# ModdedTSCircuit.net
KiCad netlist of a schematic drawn in Altium Designer
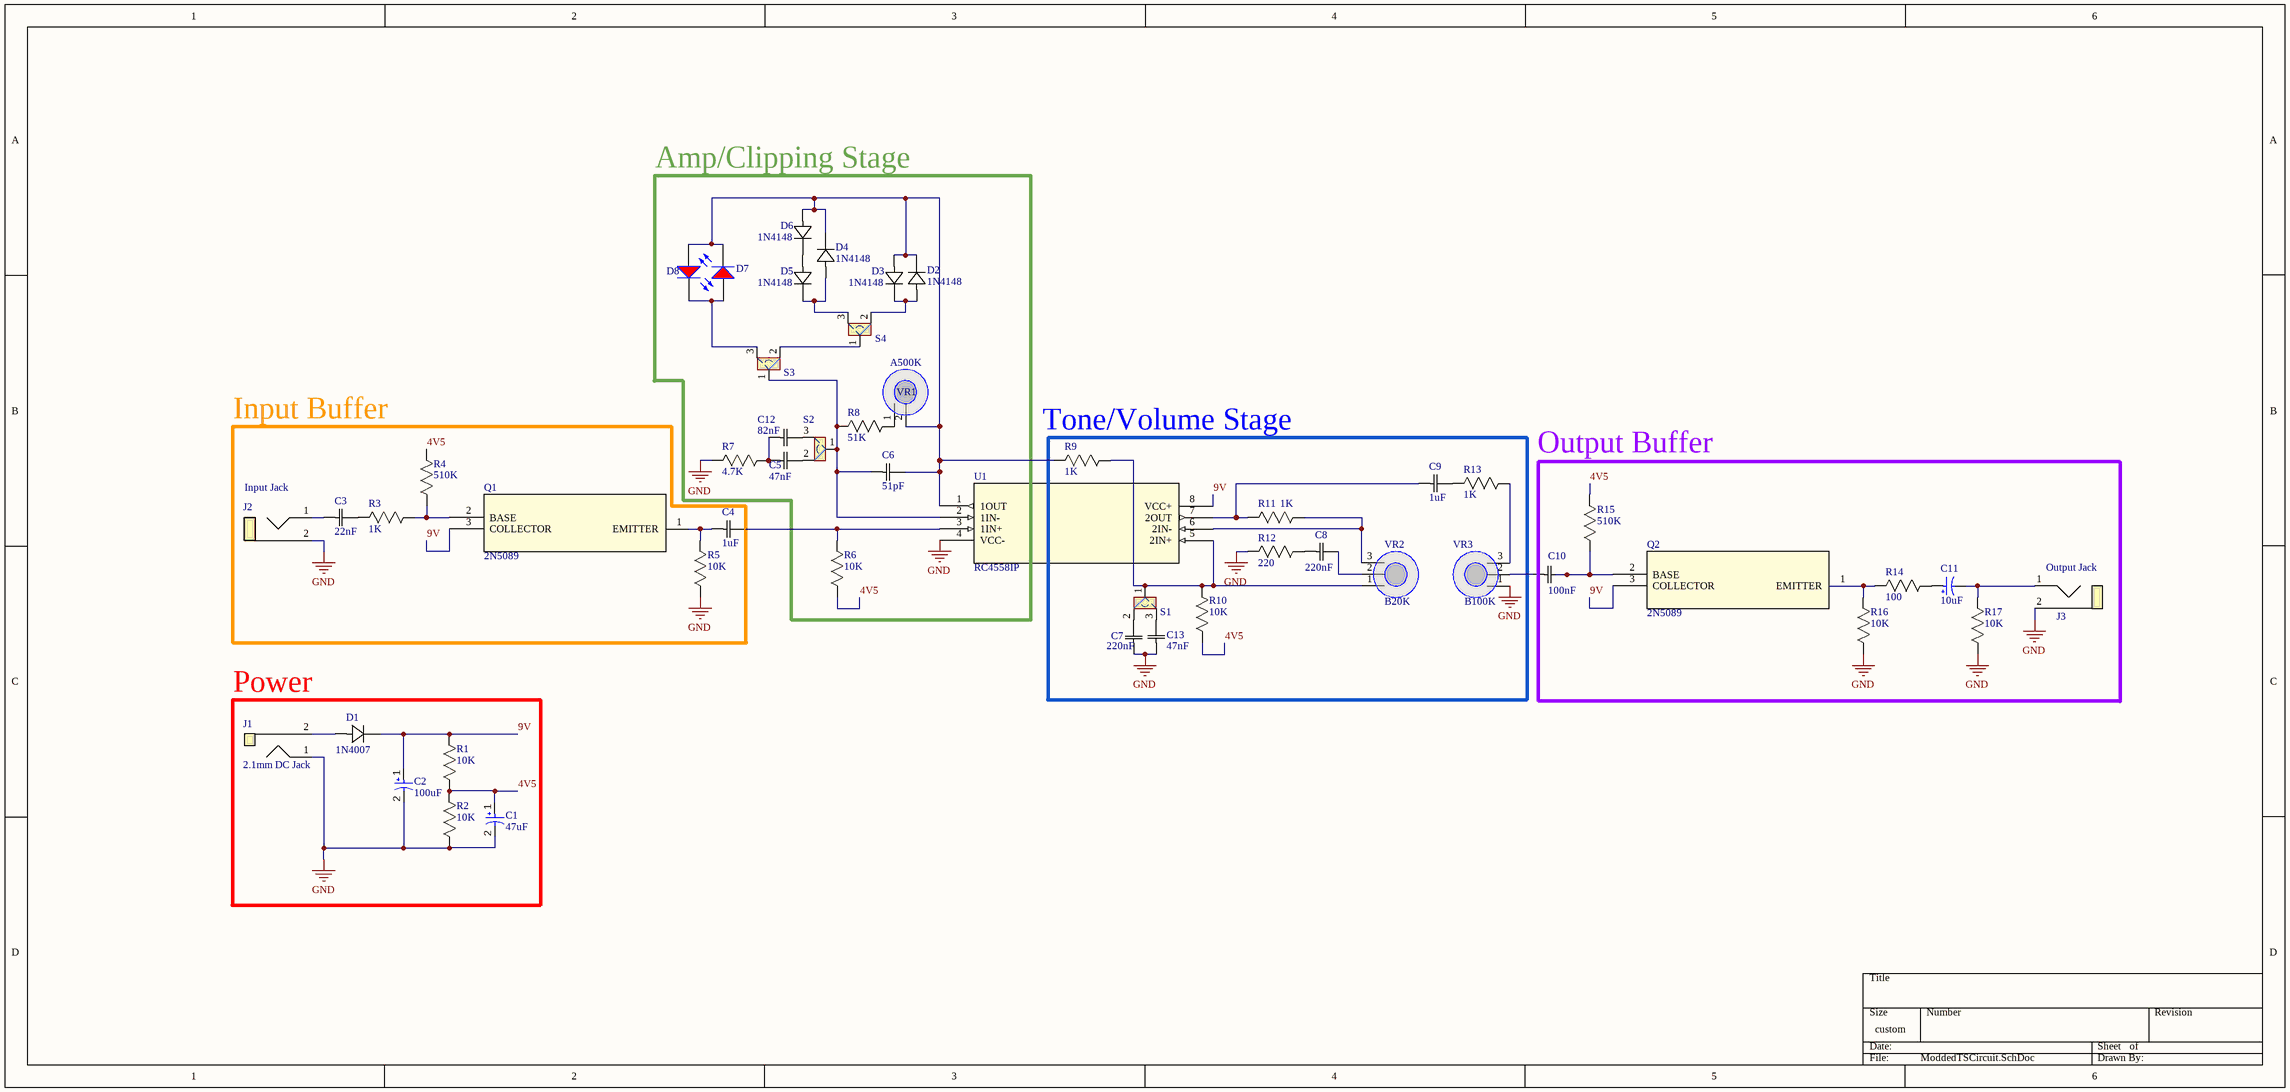
[diagram p0: ModdedTSCircuit.SchDoc]

(export (version "E")
  (design (tool "Eeschema 10.0.6"))
  (components
    (comp (ref "C1")
      (value "47uF")
      (footprint "CAP_35YXJ47M5X11")
      (description "47 µF 35 V Aluminum Electrolytic Capacitors Radial, Can 5000 Hrs @ 105°C")
      (fields
        (field (name "MANUFACTURER_PART_NUMBER") "35YXJ47M5X11")
        (field (name "COPYRIGHT") "Copyright (C) 2026 Ultra Librarian. All rights reserved.")
      )
      (libsource (lib "ModdedTSPartSymbols") (part "35YXJ47M5X11"))
    )
    (comp (ref "C2")
      (value "100uF")
      (footprint "CAP_25PX100MEFC5X11")
      (description "100 µF 25 V Aluminum Electrolytic Capacitors Radial, Can 1000 Hrs @ 105°C")
      (fields
        (field (name "MANUFACTURER_PART_NUMBER") "25PX100MEFC5X11")
        (field (name "COPYRIGHT") "Copyright (C) 2025 Ultra Librarian. All rights reserved.")
      )
      (libsource (lib "ModdedTSPartSymbols") (part "25PX100MEFC5X11"))
    )
    (comp (ref "C3")
      (value "22nF")
      (footprint "CAP_R82EC2220SH50J")
      (fields
        (field (name "MANUFACTURER_PART_NUMBER") "R82EC2220SH50J")
        (field (name "COPYRIGHT") "Copyright (C) 2026 Ultra Librarian. All rights reserved.")
      )
      (libsource (lib "ModdedTSPartSymbols") (part "R82EC2220SH50J"))
    )
    (comp (ref "C4")
      (value "1uF")
      (footprint "CAP_R82DC4100AA60K")
      (fields
        (field (name "MANUFACTURER_PART_NUMBER") "R82DC4100AA60K")
        (field (name "COPYRIGHT") "Copyright (C) 2026 Ultra Librarian. All rights reserved.")
      )
      (libsource (lib "ModdedTSPartSymbols") (part "R82DC4100AA60K"))
    )
    (comp (ref "C5")
      (value "47nF")
      (footprint "CAP_R82EC2470SH60J")
      (fields
        (field (name "MANUFACTURER_PART_NUMBER") "R82EC2470SH60J")
        (field (name "COPYRIGHT") "Copyright (C) 2026 Ultra Librarian. All rights reserved.")
      )
      (libsource (lib "ModdedTSPartSymbols") (part "R82EC2470SH60J"))
    )
    (comp (ref "C6")
      (value "51pF")
      (footprint "CAP_C315C510K3G5TA")
      (description "51 pF ±10% 25V Ceramic Capacitor C0G, NP0 Radial")
      (fields
        (field (name "MANUFACTURER_PART_NUMBER") "C315C510K3G5TA")
        (field (name "COPYRIGHT") "Copyright (C) 2026 Ultra Librarian. All rights reserved.")
      )
      (libsource (lib "ModdedTSPartSymbols") (part "C315C510K3G5TA"))
    )
    (comp (ref "C7")
      (value "220nF")
      (footprint "CAP_R82DC3220Z360J")
      (fields
        (field (name "MANUFACTURER_PART_NUMBER") "R82DC3220Z360J")
        (field (name "COPYRIGHT") "Copyright (C) 2026 Ultra Librarian. All rights reserved.")
      )
      (libsource (lib "ModdedTSPartSymbols") (part "R82DC3220Z360J"))
    )
    (comp (ref "C8")
      (value "220nF")
      (footprint "CAP_R82DC3220Z360J")
      (fields
        (field (name "MANUFACTURER_PART_NUMBER") "R82DC3220Z360J")
        (field (name "COPYRIGHT") "Copyright (C) 2026 Ultra Librarian. All rights reserved.")
      )
      (libsource (lib "ModdedTSPartSymbols") (part "R82DC3220Z360J"))
    )
    (comp (ref "C9")
      (value "1uF")
      (footprint "CAP_R82DC4100AA60K")
      (fields
        (field (name "MANUFACTURER_PART_NUMBER") "R82DC4100AA60K")
        (field (name "COPYRIGHT") "Copyright (C) 2026 Ultra Librarian. All rights reserved.")
      )
      (libsource (lib "ModdedTSPartSymbols") (part "R82DC4100AA60K"))
    )
    (comp (ref "C10")
      (value "100nF")
      (footprint "CAP_R82DC3100AA50K")
      (fields
        (field (name "MANUFACTURER_PART_NUMBER") "R82DC3100AA50K")
        (field (name "COPYRIGHT") "Copyright (C) 2026 Ultra Librarian. All rights reserved.")
      )
      (libsource (lib "ModdedTSPartSymbols") (part "R82DC3100AA50K"))
    )
    (comp (ref "C11")
      (value "10uF")
      (footprint "CAP_63PX10MEFC5X11")
      (description "10 µF 63 V Aluminum Electrolytic Capacitors Radial, Can 1000 Hrs @ 105°C")
      (fields
        (field (name "MANUFACTURER_PART_NUMBER") "63PX10MEFC5X11")
        (field (name "COPYRIGHT") "Copyright (C) 2025 Ultra Librarian. All rights reserved.")
      )
      (libsource (lib "ModdedTSPartSymbols") (part "63PX10MEFC5X11"))
    )
    (comp (ref "C12")
      (value "82nF")
      (footprint "CAP_R82EC2820SH60J")
      (fields
        (field (name "MANUFACTURER_PART_NUMBER") "R82EC2820SH60J")
        (field (name "COPYRIGHT") "Copyright (C) 2026 Ultra Librarian. All rights reserved.")
      )
      (libsource (lib "ModdedTSPartSymbols") (part "R82EC2820SH60J"))
    )
    (comp (ref "C13")
      (value "47nF")
      (footprint "CAP_R82EC2470SH60J")
      (fields
        (field (name "MANUFACTURER_PART_NUMBER") "R82EC2470SH60J")
        (field (name "COPYRIGHT") "Copyright (C) 2026 Ultra Librarian. All rights reserved.")
      )
      (libsource (lib "ModdedTSPartSymbols") (part "R82EC2470SH60J"))
    )
    (comp (ref "D1")
      (value "1N4007")
      (footprint "DIODE_1N4007FFG")
      (description "Diode 1000 V 1A Through Hole Axial")
      (fields (field (name "MANUFACTURER_PART_NUMBER") "1N4007FFG"))
      (libsource (lib "ModdedTSPartSymbols") (part "1N4007FFG"))
    )
    (comp (ref "D2")
      (value "1N4148")
      (footprint "DIODE_1N4148-T50R")
      (description "Diode 100 V 200mA Through Hole DO-35")
      (fields (field (name "MANUFACTURER_PART_NUMBER") "1N4148-T50RCT-ND"))
      (libsource (lib "ModdedTSPartSymbols") (part "1N4148-T50R"))
    )
    (comp (ref "D3")
      (value "1N4148")
      (footprint "DIODE_1N4148-T50R")
      (description "Diode 100 V 200mA Through Hole DO-35")
      (fields (field (name "MANUFACTURER_PART_NUMBER") "1N4148-T50RCT-ND"))
      (libsource (lib "ModdedTSPartSymbols") (part "1N4148-T50R"))
    )
    (comp (ref "D4")
      (value "1N4148")
      (footprint "DIODE_1N4148-T50R")
      (description "Diode 100 V 200mA Through Hole DO-35")
      (fields (field (name "MANUFACTURER_PART_NUMBER") "1N4148-T50RCT-ND"))
      (libsource (lib "ModdedTSPartSymbols") (part "1N4148-T50R"))
    )
    (comp (ref "D5")
      (value "1N4148")
      (footprint "DIODE_1N4148-T50R")
      (description "Diode 100 V 200mA Through Hole DO-35")
      (fields (field (name "MANUFACTURER_PART_NUMBER") "1N4148-T50RCT-ND"))
      (libsource (lib "ModdedTSPartSymbols") (part "1N4148-T50R"))
    )
    (comp (ref "D6")
      (value "1N4148")
      (footprint "DIODE_1N4148-T50R")
      (description "Diode 100 V 200mA Through Hole DO-35")
      (fields (field (name "MANUFACTURER_PART_NUMBER") "1N4148-T50RCT-ND"))
      (libsource (lib "ModdedTSPartSymbols") (part "1N4148-T50R"))
    )
    (comp (ref "D7")
      (value "Red, 2.1V, 60°")
      (footprint "LED_151051RS11000")
      (description "WL-TMRC Mono-color Round Color, THT, D5.9 x H8.7mm, Red, 2.1V, 60°")
      (fields
        (field (name "MANUFACTURER PART NUMBER") "151051RS11000")
        (field (name "MANUFACTURER") "Wurth Elektronik")
      )
      (libsource (lib "ModdedTSPartSymbols") (part "151051RS11000"))
    )
    (comp (ref "D8")
      (value "Red, 2.1V, 60°")
      (footprint "LED_151051RS11000")
      (description "WL-TMRC Mono-color Round Color, THT, D5.9 x H8.7mm, Red, 2.1V, 60°")
      (fields
        (field (name "MANUFACTURER PART NUMBER") "151051RS11000")
        (field (name "MANUFACTURER") "Wurth Elektronik")
      )
      (libsource (lib "ModdedTSPartSymbols") (part "151051RS11000"))
    )
    (comp (ref "J1")
      (value "2.1mm DC Jack")
      (footprint "DC_POWER_JACK_OFFBOARD")
      (description "Power Barrel Connector Jack 2.10mm ID (0.083\"), 5.50mm OD (0.217\") Chassis Mount")
      (libsource (lib "ModdedTSPartSymbols") (part "DC_POWER_JACK_OFFBOARD"))
    )
    (comp (ref "J2")
      (value "Input Jack")
      (footprint "JACK_MONO_OFFBOARD")
      (description "6.35mm (0.250\", 1/4\") - Headphone Phone Jack Mono Connector Solder Eyelet(s)")
      (libsource (lib "") (part "JACK_MONO_OFFBOARD_1"))
    )
    (comp (ref "J3")
      (value "Output Jack")
      (footprint "JACK_MONO_OFFBOARD")
      (description "6.35mm (0.250\", 1/4\") - Headphone Phone Jack Mono Connector Solder Eyelet(s)")
      (libsource (lib "ModdedTSPartSymbols") (part "JACK_MONO_OFFBOARD"))
    )
    (comp (ref "Q1")
      (value "2N5089")
      (footprint "BJT_2N5089")
      (description "Bipolar (BJT) Transistor NPN 25 V 50 mA 50MHz 625 mW Through Hole TO-92-3")
      (fields (field (name "COPYRIGHT") "Copyright (C) 2025 Ultra Librarian. All rights reserved."))
      (libsource (lib "ModdedTSPartSymbols") (part "2N5089"))
    )
    (comp (ref "Q2")
      (value "2N5089")
      (footprint "BJT_2N5089")
      (description "Bipolar (BJT) Transistor NPN 25 V 50 mA 50MHz 625 mW Through Hole TO-92-3")
      (fields (field (name "COPYRIGHT") "Copyright (C) 2025 Ultra Librarian. All rights reserved."))
      (libsource (lib "ModdedTSPartSymbols") (part "2N5089"))
    )
    (comp (ref "R1")
      (value "10K")
      (footprint "R_MFR-25FRF52-10K")
      (description "10 kOhms ±1% 0.25W, 1/4W Through Hole Resistor Axial Metal Film")
      (fields
        (field (name "MANUFACTURER_PART_NUMBER") "MFR-25FRF52-10K")
        (field (name "COPYRIGHT") "Copyright (C) 2025 Ultra Librarian. All rights reserved.")
      )
      (libsource (lib "ModdedTSPartSymbols") (part "MFR-25FRF52-10K"))
    )
    (comp (ref "R2")
      (value "10K")
      (footprint "R_MFR-25FRF52-10K")
      (description "10 kOhms ±1% 0.25W, 1/4W Through Hole Resistor Axial Metal Film")
      (fields
        (field (name "MANUFACTURER_PART_NUMBER") "MFR-25FRF52-10K")
        (field (name "COPYRIGHT") "Copyright (C) 2025 Ultra Librarian. All rights reserved.")
      )
      (libsource (lib "ModdedTSPartSymbols") (part "MFR-25FRF52-10K"))
    )
    (comp (ref "R3")
      (value "1K")
      (footprint "R_MFR-25FRF52-1K")
      (description "1 kOhms ±1% 0.25W, 1/4W Through Hole Resistor Axial Metal Film")
      (fields
        (field (name "MANUFACTURER_PART_NUMBER") "MFR-25FRF52-1K")
        (field (name "COPYRIGHT") "Copyright (C) 2025 Ultra Librarian. All rights reserved.")
      )
      (libsource (lib "ModdedTSPartSymbols") (part "MFR-25FRF52-1K"))
    )
    (comp (ref "R4")
      (value "510K")
      (footprint "R_MFR-25FTE52-510K")
      (description "510 kOhms ±1% 0.25W, 1/4W Through Hole Resistor Axial Metal Film")
      (fields
        (field (name "MANUFACTURER_PART_NUMBER") "MFR-25FTE52-510K")
        (field (name "COPYRIGHT") "Copyright (C) 2025 Ultra Librarian. All rights reserved.")
      )
      (libsource (lib "ModdedTSPartSymbols") (part "MFR-25FTE52-510K"))
    )
    (comp (ref "R5")
      (value "10K")
      (footprint "R_MFR-25FRF52-10K")
      (description "10 kOhms ±1% 0.25W, 1/4W Through Hole Resistor Axial Metal Film")
      (fields
        (field (name "MANUFACTURER_PART_NUMBER") "MFR-25FRF52-10K")
        (field (name "COPYRIGHT") "Copyright (C) 2025 Ultra Librarian. All rights reserved.")
      )
      (libsource (lib "ModdedTSPartSymbols") (part "MFR-25FRF52-10K"))
    )
    (comp (ref "R6")
      (value "10K")
      (footprint "R_MFR-25FRF52-10K")
      (description "10 kOhms ±1% 0.25W, 1/4W Through Hole Resistor Axial Metal Film")
      (fields
        (field (name "MANUFACTURER_PART_NUMBER") "MFR-25FRF52-10K")
        (field (name "COPYRIGHT") "Copyright (C) 2025 Ultra Librarian. All rights reserved.")
      )
      (libsource (lib "ModdedTSPartSymbols") (part "MFR-25FRF52-10K"))
    )
    (comp (ref "R7")
      (value "4.7K")
      (footprint "R_MFR-25FTE52-4K7")
      (description "4.7 kOhms ±1% 0.25W, 1/4W Through Hole Resistor Axial Metal Film")
      (fields
        (field (name "MANUFACTURER_PART_NUMBER") "MFR-25FTE52-4K7")
        (field (name "COPYRIGHT") "Copyright (C) 2025 Ultra Librarian. All rights reserved.")
      )
      (libsource (lib "ModdedTSPartSymbols") (part "MFR-25FTE52-4K7"))
    )
    (comp (ref "R8")
      (value "51K")
      (footprint "R_MFR-25FTE52-51K")
      (description "51 kOhms ±1% 0.25W, 1/4W Through Hole Resistor Axial Metal Film")
      (fields
        (field (name "MANUFACTURER_PART_NUMBER") "MFR-25FTE52-51K")
        (field (name "COPYRIGHT") "Copyright (C) 2025 Ultra Librarian. All rights reserved.")
      )
      (libsource (lib "ModdedTSPartSymbols") (part "MFR-25FTE52-51K"))
    )
    (comp (ref "R9")
      (value "1K")
      (footprint "R_MFR-25FRF52-1K")
      (description "1 kOhms ±1% 0.25W, 1/4W Through Hole Resistor Axial Metal Film")
      (fields
        (field (name "MANUFACTURER_PART_NUMBER") "MFR-25FRF52-1K")
        (field (name "COPYRIGHT") "Copyright (C) 2025 Ultra Librarian. All rights reserved.")
      )
      (libsource (lib "ModdedTSPartSymbols") (part "MFR-25FRF52-1K"))
    )
    (comp (ref "R10")
      (value "10K")
      (footprint "R_MFR-25FRF52-10K")
      (description "10 kOhms ±1% 0.25W, 1/4W Through Hole Resistor Axial Metal Film")
      (fields
        (field (name "MANUFACTURER_PART_NUMBER") "MFR-25FRF52-10K")
        (field (name "COPYRIGHT") "Copyright (C) 2025 Ultra Librarian. All rights reserved.")
      )
      (libsource (lib "ModdedTSPartSymbols") (part "MFR-25FRF52-10K"))
    )
    (comp (ref "R11")
      (value "1K")
      (footprint "R_MFR-25FRF52-1K")
      (description "1 kOhms ±1% 0.25W, 1/4W Through Hole Resistor Axial Metal Film")
      (fields
        (field (name "MANUFACTURER_PART_NUMBER") "MFR-25FRF52-1K")
        (field (name "COPYRIGHT") "Copyright (C) 2025 Ultra Librarian. All rights reserved.")
      )
      (libsource (lib "ModdedTSPartSymbols") (part "MFR-25FRF52-1K"))
    )
    (comp (ref "R12")
      (value "220")
      (footprint "R_MFR-25FTE52-220R")
      (description "220 Ohms ±1% 0.25W, 1/4W Through Hole Resistor Axial Metal Film")
      (fields
        (field (name "MANUFACTURER_PART_NUMBER") "MFR-25FTE52-220R")
        (field (name "COPYRIGHT") "Copyright (C) 2025 Ultra Librarian. All rights reserved.")
      )
      (libsource (lib "ModdedTSPartSymbols") (part "MFR-25FTE52-220R"))
    )
    (comp (ref "R13")
      (value "1K")
      (footprint "R_MFR-25FRF52-1K")
      (description "1 kOhms ±1% 0.25W, 1/4W Through Hole Resistor Axial Metal Film")
      (fields
        (field (name "MANUFACTURER_PART_NUMBER") "MFR-25FRF52-1K")
        (field (name "COPYRIGHT") "Copyright (C) 2025 Ultra Librarian. All rights reserved.")
      )
      (libsource (lib "ModdedTSPartSymbols") (part "MFR-25FRF52-1K"))
    )
    (comp (ref "R14")
      (value "100")
      (footprint "R_MFR-25FRF52-100R")
      (description "100 Ohms ±1% 0.25W, 1/4W Through Hole Resistor Axial Metal Film")
      (fields
        (field (name "MANUFACTURER_PART_NUMBER") "MFR-25FRF52-100R")
        (field (name "COPYRIGHT") "Copyright (C) 2025 Ultra Librarian. All rights reserved.")
      )
      (libsource (lib "ModdedTSPartSymbols") (part "MFR-25FRF52-100R"))
    )
    (comp (ref "R15")
      (value "510K")
      (footprint "R_MFR-25FTE52-510K")
      (description "510 kOhms ±1% 0.25W, 1/4W Through Hole Resistor Axial Metal Film")
      (fields
        (field (name "MANUFACTURER_PART_NUMBER") "MFR-25FTE52-510K")
        (field (name "COPYRIGHT") "Copyright (C) 2025 Ultra Librarian. All rights reserved.")
      )
      (libsource (lib "ModdedTSPartSymbols") (part "MFR-25FTE52-510K"))
    )
    (comp (ref "R16")
      (value "10K")
      (footprint "R_MFR-25FRF52-10K")
      (description "10 kOhms ±1% 0.25W, 1/4W Through Hole Resistor Axial Metal Film")
      (fields
        (field (name "MANUFACTURER_PART_NUMBER") "MFR-25FRF52-10K")
        (field (name "COPYRIGHT") "Copyright (C) 2025 Ultra Librarian. All rights reserved.")
      )
      (libsource (lib "ModdedTSPartSymbols") (part "MFR-25FRF52-10K"))
    )
    (comp (ref "R17")
      (value "10K")
      (footprint "R_MFR-25FRF52-10K")
      (description "10 kOhms ±1% 0.25W, 1/4W Through Hole Resistor Axial Metal Film")
      (fields
        (field (name "MANUFACTURER_PART_NUMBER") "MFR-25FRF52-10K")
        (field (name "COPYRIGHT") "Copyright (C) 2025 Ultra Librarian. All rights reserved.")
      )
      (libsource (lib "ModdedTSPartSymbols") (part "MFR-25FRF52-10K"))
    )
    (comp (ref "S1")
      (value "SPDT_TOGGLE_SWITCH_OFFBOARD")
      (footprint "SPDT_TOGGLE_SWITCH_OFFBOARD")
      (description "Toggle Switch SPDT Panel Mount")
      (libsource (lib "ModdedTSPartSymbols") (part "SPDT_TOGGLE_SWITCH_OFFBOARD"))
    )
    (comp (ref "S2")
      (value "SPDT_TOGGLE_SWITCH_OFFBOARD")
      (footprint "SPDT_TOGGLE_SWITCH_OFFBOARD")
      (description "Toggle Switch SPDT Panel Mount")
      (libsource (lib "") (part "SPDT_TOGGLE_SWITCH_OFFBOARD_2"))
    )
    (comp (ref "S3")
      (value "SPDT_TOGGLE_SWITCH_OFFBOARD")
      (footprint "SPDT_TOGGLE_SWITCH_OFFBOARD")
      (description "Toggle Switch SPDT Panel Mount")
      (libsource (lib "") (part "SPDT_TOGGLE_SWITCH_OFFBOARD_1"))
    )
    (comp (ref "S4")
      (value "SPDT_TOGGLE_SWITCH_OFFBOARD")
      (footprint "SPDT_TOGGLE_SWITCH_OFFBOARD")
      (description "Toggle Switch SPDT Panel Mount")
      (libsource (lib "") (part "SPDT_TOGGLE_SWITCH_OFFBOARD_1"))
    )
    (comp (ref "U1")
      (value "RC4558IP")
      (footprint "OPAMP_RC4558IP")
      (description "Standard (General Purpose) Amplifier 2 Circuit Differential 8-PDIP")
      (fields (field (name "COPYRIGHT") "Copyright (C) 2025 Ultra Librarian. All rights reserved."))
      (libsource (lib "ModdedTSPartSymbols") (part "RC4558IP"))
    )
    (comp (ref "VR1")
      (value "A500K")
      (footprint "POT_500K_LOG_OFFBOARD")
      (description "A500K, 16mm Potentiometers - 18T Knurled Shaft - Solder Lug")
      (libsource (lib "ModdedTSPartSymbols") (part "POT_500K_LOG_OFFBOARD"))
    )
    (comp (ref "VR2")
      (value "B20K")
      (footprint "POT_20K_LIN_OFFBOARD")
      (description "B20K, 16mm Potentiometers - 18T Knurled Shaft - Solder Lug")
      (libsource (lib "ModdedTSPartSymbols") (part "POT_20K_LIN_OFFBOARD"))
    )
    (comp (ref "VR3")
      (value "B100K")
      (footprint "POT_100K_LIN_OFFBOARD")
      (description "B100K, 16mm Potentiometers - 18T Knurled Shaft - Solder Lug")
      (libsource (lib "ModdedTSPartSymbols") (part "POT_100K_LIN_OFFBOARD"))
    )
  )
  (nets
    (net (code "1") (name "/4V5") (class "Default")
      (node (ref "C1") (pin "1") (pinfunction "1_1") (pintype "passive"))
      (node (ref "R1") (pin "1") (pinfunction "1_1") (pintype "passive"))
      (node (ref "R10") (pin "1") (pinfunction "1_1") (pintype "passive"))
      (node (ref "R15") (pin "2") (pinfunction "2_2") (pintype "passive"))
      (node (ref "R2") (pin "2") (pinfunction "2_2") (pintype "passive"))
      (node (ref "R4") (pin "2") (pinfunction "2_2") (pintype "passive"))
      (node (ref "R6") (pin "1") (pinfunction "1_1") (pintype "passive"))
    )
    (net (code "2") (name "/9V") (class "Default")
      (node (ref "C2") (pin "1") (pinfunction "1_1") (pintype "passive"))
      (node (ref "D1") (pin "1") (pinfunction "1_1") (pintype "passive"))
      (node (ref "Q1") (pin "3") (pinfunction "COLLECTOR_3") (pintype "passive"))
      (node (ref "Q2") (pin "3") (pinfunction "COLLECTOR_3") (pintype "passive"))
      (node (ref "R1") (pin "2") (pinfunction "2_2") (pintype "passive"))
      (node (ref "U1") (pin "8") (pinfunction "VCC+_8") (pintype "power_in"))
    )
    (net (code "3") (name "GND") (class "Default")
      (node (ref "C1") (pin "2") (pinfunction "2_2") (pintype "passive"))
      (node (ref "C13") (pin "1") (pinfunction "1_1") (pintype "passive"))
      (node (ref "C2") (pin "2") (pinfunction "2_2") (pintype "passive"))
      (node (ref "C7") (pin "1") (pinfunction "1_1") (pintype "passive"))
      (node (ref "J1") (pin "1") (pinfunction "TIP_1") (pintype "passive"))
      (node (ref "J2") (pin "2") (pinfunction "SLEEVE_2") (pintype "passive"))
      (node (ref "J3") (pin "2") (pinfunction "SLEEVE_2") (pintype "passive"))
      (node (ref "R12") (pin "1") (pinfunction "1_1") (pintype "passive"))
      (node (ref "R16") (pin "1") (pinfunction "1_1") (pintype "passive"))
      (node (ref "R17") (pin "1") (pinfunction "1_1") (pintype "passive"))
      (node (ref "R2") (pin "1") (pinfunction "1_1") (pintype "passive"))
      (node (ref "R5") (pin "1") (pinfunction "1_1") (pintype "passive"))
      (node (ref "R7") (pin "1") (pinfunction "1_1") (pintype "passive"))
      (node (ref "U1") (pin "4") (pinfunction "VCC-_4") (pintype "power_in"))
      (node (ref "VR3") (pin "1") (pinfunction "1_1") (pintype "passive"))
    )
    (net (code "4") (name "Net-(C3-Pad2)") (class "Default")
      (node (ref "C3") (pin "2") (pinfunction "2_2") (pintype "passive"))
      (node (ref "R3") (pin "1") (pinfunction "1_1") (pintype "passive"))
    )
    (net (code "5") (name "Net-(C5-Pad2)") (class "Default")
      (node (ref "C5") (pin "2") (pinfunction "2_2") (pintype "passive"))
      (node (ref "S2") (pin "2") (pinfunction "2_2") (pintype "passive"))
    )
    (net (code "6") (name "Net-(C7-Pad2)") (class "Default")
      (node (ref "C7") (pin "2") (pinfunction "2_2") (pintype "passive"))
      (node (ref "S1") (pin "2") (pinfunction "2_2") (pintype "passive"))
    )
    (net (code "7") (name "Net-(C8-Pad1)") (class "Default")
      (node (ref "C8") (pin "1") (pinfunction "1_1") (pintype "passive"))
      (node (ref "R12") (pin "2") (pinfunction "2_2") (pintype "passive"))
    )
    (net (code "8") (name "Net-(C8-Pad2)") (class "Default")
      (node (ref "C8") (pin "2") (pinfunction "2_2") (pintype "passive"))
      (node (ref "VR2") (pin "2") (pinfunction "2_2") (pintype "passive"))
    )
    (net (code "9") (name "Net-(C9-Pad2)") (class "Default")
      (node (ref "C9") (pin "2") (pinfunction "2_2") (pintype "passive"))
      (node (ref "R13") (pin "1") (pinfunction "1_1") (pintype "passive"))
    )
    (net (code "10") (name "Net-(C10-Pad1)") (class "Default")
      (node (ref "C10") (pin "1") (pinfunction "1_1") (pintype "passive"))
      (node (ref "VR3") (pin "2") (pinfunction "2_2") (pintype "passive"))
    )
    (net (code "11") (name "Net-(C11-Pad1)") (class "Default")
      (node (ref "C11") (pin "1") (pinfunction "1_1") (pintype "passive"))
      (node (ref "R14") (pin "2") (pinfunction "2_2") (pintype "passive"))
    )
    (net (code "12") (name "Net-(C12-Pad1)") (class "Default")
      (node (ref "C12") (pin "1") (pinfunction "1_1") (pintype "passive"))
      (node (ref "C5") (pin "1") (pinfunction "1_1") (pintype "passive"))
      (node (ref "R7") (pin "2") (pinfunction "2_2") (pintype "passive"))
    )
    (net (code "13") (name "Net-(C12-Pad2)") (class "Default")
      (node (ref "C12") (pin "2") (pinfunction "2_2") (pintype "passive"))
      (node (ref "S2") (pin "3") (pinfunction "3_3") (pintype "passive"))
    )
    (net (code "14") (name "Net-(C13-Pad2)") (class "Default")
      (node (ref "C13") (pin "2") (pinfunction "2_2") (pintype "passive"))
      (node (ref "S1") (pin "3") (pinfunction "3_3") (pintype "passive"))
    )
    (net (code "15") (name "Net-(D2-Pad2)") (class "Default")
      (node (ref "D2") (pin "2") (pinfunction "2_2") (pintype "passive"))
      (node (ref "D3") (pin "1") (pinfunction "1_1") (pintype "passive"))
      (node (ref "S4") (pin "2") (pinfunction "2_2") (pintype "passive"))
    )
    (net (code "16") (name "Net-(D4-Pad2)") (class "Default")
      (node (ref "D4") (pin "2") (pinfunction "2_2") (pintype "passive"))
      (node (ref "D5") (pin "1") (pinfunction "1_1") (pintype "passive"))
      (node (ref "S4") (pin "3") (pinfunction "3_3") (pintype "passive"))
    )
    (net (code "17") (name "Net-(D5-Pad2)") (class "Default")
      (node (ref "D5") (pin "2") (pinfunction "2_2") (pintype "passive"))
      (node (ref "D6") (pin "1") (pinfunction "1_1") (pintype "passive"))
    )
    (net (code "18") (name "Net-(D7-A)") (class "Default")
      (node (ref "D7") (pin "1") (pinfunction "A_1") (pintype "passive"))
      (node (ref "D8") (pin "2") (pinfunction "K_2") (pintype "passive"))
      (node (ref "S3") (pin "3") (pinfunction "3_3") (pintype "passive"))
    )
    (net (code "19") (name "Net-(D7-K)") (class "Default")
      (node (ref "C6") (pin "2") (pinfunction "2_2") (pintype "passive"))
      (node (ref "D2") (pin "1") (pinfunction "1_1") (pintype "passive"))
      (node (ref "D3") (pin "2") (pinfunction "2_2") (pintype "passive"))
      (node (ref "D4") (pin "1") (pinfunction "1_1") (pintype "passive"))
      (node (ref "D6") (pin "2") (pinfunction "2_2") (pintype "passive"))
      (node (ref "D7") (pin "2") (pinfunction "K_2") (pintype "passive"))
      (node (ref "D8") (pin "1") (pinfunction "A_1") (pintype "passive"))
      (node (ref "R9") (pin "1") (pinfunction "1_1") (pintype "passive"))
      (node (ref "U1") (pin "1") (pinfunction "1OUT_1") (pintype "output"))
      (node (ref "VR1") (pin "2") (pinfunction "2_2") (pintype "passive"))
    )
    (net (code "20") (name "Net-(J1-SLEEVE)") (class "Default")
      (node (ref "D1") (pin "2") (pinfunction "2_2") (pintype "passive"))
      (node (ref "J1") (pin "2") (pinfunction "SLEEVE_2") (pintype "passive"))
    )
    (net (code "21") (name "Net-(J2-TIP)") (class "Default")
      (node (ref "C3") (pin "1") (pinfunction "1_1") (pintype "passive"))
      (node (ref "J2") (pin "1") (pinfunction "TIP_1") (pintype "passive"))
    )
    (net (code "22") (name "Net-(J3-TIP)") (class "Default")
      (node (ref "C11") (pin "2") (pinfunction "2_2") (pintype "passive"))
      (node (ref "J3") (pin "1") (pinfunction "TIP_1") (pintype "passive"))
      (node (ref "R17") (pin "2") (pinfunction "2_2") (pintype "passive"))
    )
    (net (code "23") (name "Net-(Q1-BASE)") (class "Default")
      (node (ref "Q1") (pin "2") (pinfunction "BASE_2") (pintype "passive"))
      (node (ref "R3") (pin "2") (pinfunction "2_2") (pintype "passive"))
      (node (ref "R4") (pin "1") (pinfunction "1_1") (pintype "passive"))
    )
    (net (code "24") (name "Net-(Q1-EMITTER)") (class "Default")
      (node (ref "C4") (pin "1") (pinfunction "1_1") (pintype "passive"))
      (node (ref "Q1") (pin "1") (pinfunction "EMITTER_1") (pintype "passive"))
      (node (ref "R5") (pin "2") (pinfunction "2_2") (pintype "passive"))
    )
    (net (code "25") (name "Net-(Q2-BASE)") (class "Default")
      (node (ref "C10") (pin "2") (pinfunction "2_2") (pintype "passive"))
      (node (ref "Q2") (pin "2") (pinfunction "BASE_2") (pintype "passive"))
      (node (ref "R15") (pin "1") (pinfunction "1_1") (pintype "passive"))
    )
    (net (code "26") (name "Net-(Q2-EMITTER)") (class "Default")
      (node (ref "Q2") (pin "1") (pinfunction "EMITTER_1") (pintype "passive"))
      (node (ref "R14") (pin "1") (pinfunction "1_1") (pintype "passive"))
      (node (ref "R16") (pin "2") (pinfunction "2_2") (pintype "passive"))
    )
    (net (code "27") (name "Net-(R8-Pad2)") (class "Default")
      (node (ref "R8") (pin "2") (pinfunction "2_2") (pintype "passive"))
      (node (ref "VR1") (pin "1") (pinfunction "1_1") (pintype "passive"))
    )
    (net (code "28") (name "Net-(R13-Pad2)") (class "Default")
      (node (ref "R13") (pin "2") (pinfunction "2_2") (pintype "passive"))
      (node (ref "VR3") (pin "3") (pinfunction "3_3") (pintype "passive"))
    )
    (net (code "29") (name "Net-(S3-Pad2)") (class "Default")
      (node (ref "S3") (pin "2") (pinfunction "2_2") (pintype "passive"))
      (node (ref "S4") (pin "1") (pinfunction "1_1") (pintype "passive"))
    )
    (net (code "30") (name "Net-(U1-1IN+)") (class "Default")
      (node (ref "C4") (pin "2") (pinfunction "2_2") (pintype "passive"))
      (node (ref "R6") (pin "2") (pinfunction "2_2") (pintype "passive"))
      (node (ref "U1") (pin "3") (pinfunction "1IN+_3") (pintype "input"))
    )
    (net (code "31") (name "Net-(U1-1IN-)") (class "Default")
      (node (ref "C6") (pin "1") (pinfunction "1_1") (pintype "passive"))
      (node (ref "R8") (pin "1") (pinfunction "1_1") (pintype "passive"))
      (node (ref "S2") (pin "1") (pinfunction "1_1") (pintype "passive"))
      (node (ref "S3") (pin "1") (pinfunction "1_1") (pintype "passive"))
      (node (ref "U1") (pin "2") (pinfunction "1IN-_2") (pintype "input"))
    )
    (net (code "32") (name "Net-(U1-2IN+)") (class "Default")
      (node (ref "R10") (pin "2") (pinfunction "2_2") (pintype "passive"))
      (node (ref "R9") (pin "2") (pinfunction "2_2") (pintype "passive"))
      (node (ref "S1") (pin "1") (pinfunction "1_1") (pintype "passive"))
      (node (ref "U1") (pin "5") (pinfunction "2IN+_5") (pintype "input"))
      (node (ref "VR2") (pin "1") (pinfunction "1_1") (pintype "passive"))
    )
    (net (code "33") (name "Net-(U1-2IN-)") (class "Default")
      (node (ref "R11") (pin "2") (pinfunction "2_2") (pintype "passive"))
      (node (ref "U1") (pin "6") (pinfunction "2IN-_6") (pintype "input"))
      (node (ref "VR2") (pin "3") (pinfunction "3_3") (pintype "passive"))
    )
    (net (code "34") (name "Net-(U1-2OUT)") (class "Default")
      (node (ref "C9") (pin "1") (pinfunction "1_1") (pintype "passive"))
      (node (ref "R11") (pin "1") (pinfunction "1_1") (pintype "passive"))
      (node (ref "U1") (pin "7") (pinfunction "2OUT_7") (pintype "output"))
    )
  )
)
